# SilentStepStick-TMC2100_v10.net
KiCad netlist of a schematic drawn in EAGLE
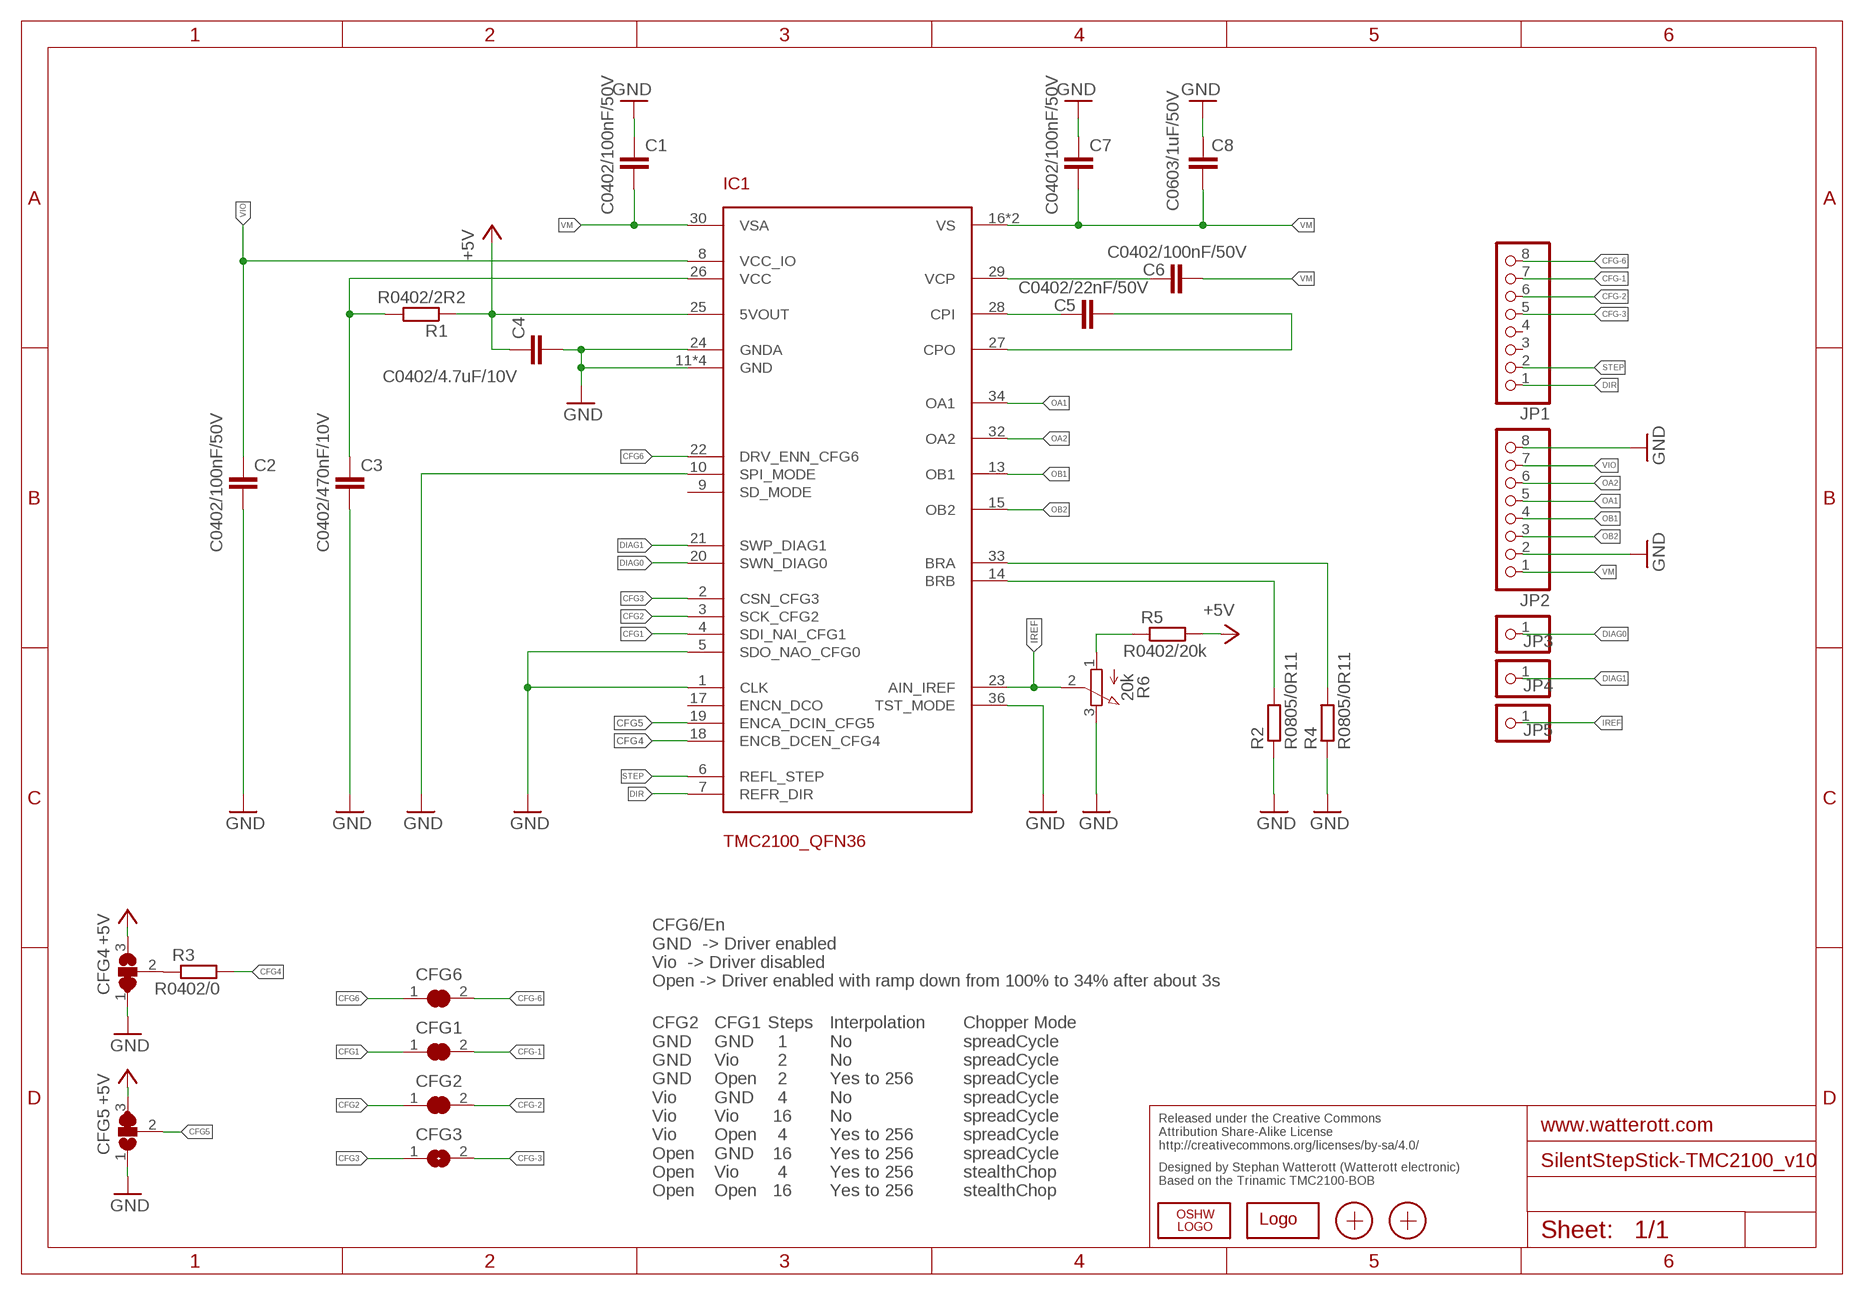
[diagram p0: schematic, sheet 1]

(export (version "E")
  (design (tool "Eeschema 10.0.6"))
  (components
    (comp (ref "C1")
      (value "C0402/100nF/50V")
      (footprint "eagle-import:C0402")
      (libsource (lib "eagle-import") (part "C-EUC0402"))
    )
    (comp (ref "C2")
      (value "C0402/100nF/50V")
      (footprint "eagle-import:C0402")
      (libsource (lib "eagle-import") (part "C-EUC0402"))
    )
    (comp (ref "C3")
      (value "C0402/470nF/10V")
      (footprint "eagle-import:C0402")
      (libsource (lib "eagle-import") (part "C-EUC0402"))
    )
    (comp (ref "C4")
      (value "C0402/4.7uF/10V")
      (footprint "eagle-import:C0402")
      (libsource (lib "eagle-import") (part "C-EUC0402"))
    )
    (comp (ref "C5")
      (value "C0402/22nF/50V")
      (footprint "eagle-import:C0402")
      (libsource (lib "eagle-import") (part "C-EUC0402"))
    )
    (comp (ref "C6")
      (value "C0402/100nF/50V")
      (footprint "eagle-import:C0402")
      (libsource (lib "eagle-import") (part "C-EUC0402"))
    )
    (comp (ref "C7")
      (value "C0402/100nF/50V")
      (footprint "eagle-import:C0402")
      (libsource (lib "eagle-import") (part "C-EUC0402"))
    )
    (comp (ref "C8")
      (value "C0603/1uF/50V")
      (footprint "eagle-import:C0603")
      (libsource (lib "eagle-import") (part "C-EUC0603"))
    )
    (comp (ref "CFG1")
      (value "JUMPER2-0201")
      (footprint "eagle-import:JUMPER2-0201")
      (libsource (lib "eagle-import") (part "JUMPER2-0201"))
    )
    (comp (ref "CFG2")
      (value "JUMPER2-0201")
      (footprint "eagle-import:JUMPER2-0201")
      (libsource (lib "eagle-import") (part "JUMPER2-0201"))
    )
    (comp (ref "CFG3")
      (value "JUMPER2-0201")
      (footprint "eagle-import:JUMPER2-0201")
      (libsource (lib "eagle-import") (part "JUMPER2-0201"))
    )
    (comp (ref "CFG4")
      (value "JUMPER3-0201-NC")
      (footprint "eagle-import:JUMPER3-0201_NC")
      (libsource (lib "eagle-import") (part "JUMPER3-0201-NC"))
    )
    (comp (ref "CFG5")
      (value "JUMPER3-0201")
      (footprint "eagle-import:JUMPER3-0201")
      (libsource (lib "eagle-import") (part "JUMPER3-0201"))
    )
    (comp (ref "CFG6")
      (value "JUMPER2-0201")
      (footprint "eagle-import:JUMPER2-0201")
      (libsource (lib "eagle-import") (part "JUMPER2-0201"))
    )
    (comp (ref "IC1")
      (value "TMC2100_QFN36")
      (footprint "eagle-import:QFN36")
      (libsource (lib "eagle-import") (part "TMC2100_QFN36"))
    )
    (comp (ref "JP1")
      (value "PINHD-1X08_2.54-S")
      (footprint "eagle-import:1X08-S")
      (libsource (lib "eagle-import") (part "PINHD-1X08_2.54-S"))
    )
    (comp (ref "JP2")
      (value "PINHD-1X08_2.54-S")
      (footprint "eagle-import:1X08-S")
      (libsource (lib "eagle-import") (part "PINHD-1X08_2.54-S"))
    )
    (comp (ref "JP3")
      (value "PINHD-1X1")
      (footprint "eagle-import:1X01")
      (libsource (lib "eagle-import") (part "PINHD-1X1"))
    )
    (comp (ref "JP4")
      (value "PINHD-1X1")
      (footprint "eagle-import:1X01")
      (libsource (lib "eagle-import") (part "PINHD-1X1"))
    )
    (comp (ref "JP5")
      (value "PINHD-1X1")
      (footprint "eagle-import:1X01")
      (libsource (lib "eagle-import") (part "PINHD-1X1"))
    )
    (comp (ref "LOGO1")
      (value "OSHW_LOGOX0070")
      (footprint "eagle-import:OSHW_6X70")
      (libsource (lib "eagle-import") (part "OSHW_LOGOX0070"))
    )
    (comp (ref "LOGO2")
      (value "LOGO-S_PLACE_M")
      (footprint "eagle-import:SPARK_TPLACE_M")
      (libsource (lib "eagle-import") (part "LOGO-S_PLACE_M"))
    )
    (comp (ref "R1")
      (value "R0402/2R2")
      (footprint "eagle-import:R0402")
      (libsource (lib "eagle-import") (part "R-EU_R0402"))
    )
    (comp (ref "R2")
      (value "R0805/0R11")
      (footprint "eagle-import:M0805")
      (libsource (lib "eagle-import") (part "R-EU_M0805"))
    )
    (comp (ref "R3")
      (value "R0402/0")
      (footprint "eagle-import:R0402")
      (libsource (lib "eagle-import") (part "R-EU_R0402"))
    )
    (comp (ref "R4")
      (value "R0805/0R11")
      (footprint "eagle-import:M0805")
      (libsource (lib "eagle-import") (part "R-EU_M0805"))
    )
    (comp (ref "R5")
      (value "R0402/20k")
      (footprint "eagle-import:R0402")
      (libsource (lib "eagle-import") (part "R-EU_R0402"))
    )
    (comp (ref "R6")
      (value "20k")
      (footprint "eagle-import:POT_EVM3R")
      (libsource (lib "eagle-import") (part "POTEVM3R"))
    )
    (comp (ref "X1")
      (value "PASSER-07")
      (footprint "eagle-import:PASSER_07MM")
      (libsource (lib "eagle-import") (part "PASSER-07"))
    )
    (comp (ref "X2")
      (value "PASSER-07")
      (footprint "eagle-import:PASSER_07MM")
      (libsource (lib "eagle-import") (part "PASSER-07"))
    )
  )
  (nets
    (net (code "1") (name "+5V") (class "Default")
      (node (ref "C4") (pin "1") (pinfunction "1_1") (pintype "passive"))
      (node (ref "CFG4") (pin "3") (pinfunction "3_3") (pintype "passive"))
      (node (ref "CFG5") (pin "3") (pinfunction "3_3") (pintype "passive"))
      (node (ref "IC1") (pin "25") (pinfunction "5VOUT_25") (pintype "bidirectional"))
      (node (ref "R1") (pin "1") (pinfunction "1_1") (pintype "passive"))
      (node (ref "R5") (pin "2") (pinfunction "2_2") (pintype "passive"))
    )
    (net (code "2") (name "CFG-1") (class "Default")
      (node (ref "CFG1") (pin "2") (pinfunction "2_2") (pintype "passive"))
      (node (ref "JP1") (pin "7") (pinfunction "7_7") (pintype "passive"))
    )
    (net (code "3") (name "CFG-2") (class "Default")
      (node (ref "CFG2") (pin "2") (pinfunction "2_2") (pintype "passive"))
      (node (ref "JP1") (pin "6") (pinfunction "6_6") (pintype "passive"))
    )
    (net (code "4") (name "CFG-3") (class "Default")
      (node (ref "CFG3") (pin "2") (pinfunction "2_2") (pintype "passive"))
      (node (ref "JP1") (pin "5") (pinfunction "5_5") (pintype "passive"))
    )
    (net (code "5") (name "CFG-6") (class "Default")
      (node (ref "CFG6") (pin "2") (pinfunction "2_2") (pintype "passive"))
      (node (ref "JP1") (pin "8") (pinfunction "8_8") (pintype "passive"))
    )
    (net (code "6") (name "CFG1") (class "Default")
      (node (ref "CFG1") (pin "1") (pinfunction "1_1") (pintype "passive"))
      (node (ref "IC1") (pin "4") (pinfunction "SDI_NAI_CFG1_4") (pintype "bidirectional"))
    )
    (net (code "7") (name "CFG2") (class "Default")
      (node (ref "CFG2") (pin "1") (pinfunction "1_1") (pintype "passive"))
      (node (ref "IC1") (pin "3") (pinfunction "SCK_CFG2_3") (pintype "bidirectional"))
    )
    (net (code "8") (name "CFG3") (class "Default")
      (node (ref "CFG3") (pin "1") (pinfunction "1_1") (pintype "passive"))
      (node (ref "IC1") (pin "2") (pinfunction "CSN_CFG3_2") (pintype "bidirectional"))
    )
    (net (code "9") (name "CFG4") (class "Default")
      (node (ref "IC1") (pin "18") (pinfunction "ENCB_DCEN_CFG4_18") (pintype "bidirectional"))
      (node (ref "R3") (pin "2") (pinfunction "2_2") (pintype "passive"))
    )
    (net (code "10") (name "CFG5") (class "Default")
      (node (ref "CFG5") (pin "2") (pinfunction "2_2") (pintype "passive"))
      (node (ref "IC1") (pin "19") (pinfunction "ENCA_DCIN_CFG5_19") (pintype "bidirectional"))
    )
    (net (code "11") (name "CFG6") (class "Default")
      (node (ref "CFG6") (pin "1") (pinfunction "1_1") (pintype "passive"))
      (node (ref "IC1") (pin "22") (pinfunction "DRV_ENN_CFG6_22") (pintype "bidirectional"))
    )
    (net (code "12") (name "DIAG0") (class "Default")
      (node (ref "IC1") (pin "20") (pinfunction "SWN_DIAG0_20") (pintype "bidirectional"))
      (node (ref "JP3") (pin "1") (pinfunction "1_1") (pintype "passive"))
    )
    (net (code "13") (name "DIAG1") (class "Default")
      (node (ref "IC1") (pin "21") (pinfunction "SWP_DIAG1_21") (pintype "bidirectional"))
      (node (ref "JP4") (pin "1") (pinfunction "1_1") (pintype "passive"))
    )
    (net (code "14") (name "DIR") (class "Default")
      (node (ref "IC1") (pin "7") (pinfunction "REFR_DIR_7") (pintype "bidirectional"))
      (node (ref "JP1") (pin "1") (pinfunction "1_1") (pintype "passive"))
    )
    (net (code "15") (name "GND") (class "Default")
      (node (ref "C1") (pin "1") (pinfunction "1_1") (pintype "passive"))
      (node (ref "C2") (pin "2") (pinfunction "2_2") (pintype "passive"))
      (node (ref "C3") (pin "2") (pinfunction "2_2") (pintype "passive"))
      (node (ref "C4") (pin "2") (pinfunction "2_2") (pintype "passive"))
      (node (ref "C7") (pin "1") (pinfunction "1_1") (pintype "passive"))
      (node (ref "C8") (pin "2") (pinfunction "2_2") (pintype "passive"))
      (node (ref "CFG4") (pin "1") (pinfunction "1_1") (pintype "passive"))
      (node (ref "CFG5") (pin "1") (pinfunction "1_1") (pintype "passive"))
      (node (ref "IC1") (pin "1") (pinfunction "CLK_1") (pintype "bidirectional"))
      (node (ref "IC1") (pin "10") (pinfunction "SPI_MODE_10") (pintype "bidirectional"))
      (node (ref "IC1") (pin "11") (pinfunction "GND_11") (pintype "bidirectional"))
      (node (ref "IC1") (pin "12") (pinfunction "GND_12") (pintype "bidirectional"))
      (node (ref "IC1") (pin "24") (pinfunction "GNDA_24") (pintype "bidirectional"))
      (node (ref "IC1") (pin "35") (pinfunction "GND_35") (pintype "bidirectional"))
      (node (ref "IC1") (pin "36") (pinfunction "TST_MODE_36") (pintype "bidirectional"))
      (node (ref "IC1") (pin "5") (pinfunction "SDO_NAO_CFG0_5") (pintype "bidirectional"))
      (node (ref "IC1") (pin "GND_PAD") (pinfunction "GND_GND_PAD") (pintype "bidirectional"))
      (node (ref "JP2") (pin "2") (pinfunction "2_2") (pintype "passive"))
      (node (ref "JP2") (pin "8") (pinfunction "8_8") (pintype "passive"))
      (node (ref "R2") (pin "1") (pinfunction "1_1") (pintype "passive"))
      (node (ref "R4") (pin "1") (pinfunction "1_1") (pintype "passive"))
      (node (ref "R6") (pin "3") (pinfunction "E_3") (pintype "passive"))
    )
    (net (code "16") (name "IREF") (class "Default")
      (node (ref "IC1") (pin "23") (pinfunction "AIN_IREF_23") (pintype "bidirectional"))
      (node (ref "JP5") (pin "1") (pinfunction "1_1") (pintype "passive"))
      (node (ref "R6") (pin "2") (pinfunction "S_2") (pintype "passive"))
    )
    (net (code "17") (name "Net-(CFG4-Pad2)") (class "Default")
      (node (ref "CFG4") (pin "2") (pinfunction "2_2") (pintype "passive"))
      (node (ref "R3") (pin "1") (pinfunction "1_1") (pintype "passive"))
    )
    (net (code "18") (name "Net-(IC1-BRA)") (class "Default")
      (node (ref "IC1") (pin "33") (pinfunction "BRA_33") (pintype "bidirectional"))
      (node (ref "R4") (pin "2") (pinfunction "2_2") (pintype "passive"))
    )
    (net (code "19") (name "Net-(IC1-BRB)") (class "Default")
      (node (ref "IC1") (pin "14") (pinfunction "BRB_14") (pintype "bidirectional"))
      (node (ref "R2") (pin "2") (pinfunction "2_2") (pintype "passive"))
    )
    (net (code "20") (name "Net-(IC1-CPI)") (class "Default")
      (node (ref "C5") (pin "1") (pinfunction "1_1") (pintype "passive"))
      (node (ref "IC1") (pin "28") (pinfunction "CPI_28") (pintype "bidirectional"))
    )
    (net (code "21") (name "Net-(IC1-CPO)") (class "Default")
      (node (ref "C5") (pin "2") (pinfunction "2_2") (pintype "passive"))
      (node (ref "IC1") (pin "27") (pinfunction "CPO_27") (pintype "bidirectional"))
    )
    (net (code "22") (name "Net-(IC1-VCC)") (class "Default")
      (node (ref "C3") (pin "1") (pinfunction "1_1") (pintype "passive"))
      (node (ref "IC1") (pin "26") (pinfunction "VCC_26") (pintype "bidirectional"))
      (node (ref "R1") (pin "2") (pinfunction "2_2") (pintype "passive"))
    )
    (net (code "23") (name "Net-(IC1-VCP)") (class "Default")
      (node (ref "C6") (pin "1") (pinfunction "1_1") (pintype "passive"))
      (node (ref "IC1") (pin "29") (pinfunction "VCP_29") (pintype "bidirectional"))
    )
    (net (code "24") (name "Net-(R6-A)") (class "Default")
      (node (ref "R5") (pin "1") (pinfunction "1_1") (pintype "passive"))
      (node (ref "R6") (pin "1") (pinfunction "A_1") (pintype "passive"))
    )
    (net (code "25") (name "OA1") (class "Default")
      (node (ref "IC1") (pin "34") (pinfunction "OA1_34") (pintype "bidirectional"))
      (node (ref "JP2") (pin "5") (pinfunction "5_5") (pintype "passive"))
    )
    (net (code "26") (name "OA2") (class "Default")
      (node (ref "IC1") (pin "32") (pinfunction "OA2_32") (pintype "bidirectional"))
      (node (ref "JP2") (pin "6") (pinfunction "6_6") (pintype "passive"))
    )
    (net (code "27") (name "OB1") (class "Default")
      (node (ref "IC1") (pin "13") (pinfunction "OB1_13") (pintype "bidirectional"))
      (node (ref "JP2") (pin "4") (pinfunction "4_4") (pintype "passive"))
    )
    (net (code "28") (name "OB2") (class "Default")
      (node (ref "IC1") (pin "15") (pinfunction "OB2_15") (pintype "bidirectional"))
      (node (ref "JP2") (pin "3") (pinfunction "3_3") (pintype "passive"))
    )
    (net (code "29") (name "STEP") (class "Default")
      (node (ref "IC1") (pin "6") (pinfunction "REFL_STEP_6") (pintype "bidirectional"))
      (node (ref "JP1") (pin "2") (pinfunction "2_2") (pintype "passive"))
    )
    (net (code "30") (name "VIO") (class "Default")
      (node (ref "C2") (pin "1") (pinfunction "1_1") (pintype "passive"))
      (node (ref "IC1") (pin "8") (pinfunction "VCC_IO_8") (pintype "bidirectional"))
      (node (ref "JP2") (pin "7") (pinfunction "7_7") (pintype "passive"))
    )
    (net (code "31") (name "VM") (class "Default")
      (node (ref "C1") (pin "2") (pinfunction "2_2") (pintype "passive"))
      (node (ref "C6") (pin "2") (pinfunction "2_2") (pintype "passive"))
      (node (ref "C7") (pin "2") (pinfunction "2_2") (pintype "passive"))
      (node (ref "C8") (pin "1") (pinfunction "1_1") (pintype "passive"))
      (node (ref "IC1") (pin "16") (pinfunction "VS_16") (pintype "bidirectional"))
      (node (ref "IC1") (pin "30") (pinfunction "VSA_30") (pintype "bidirectional"))
      (node (ref "IC1") (pin "31") (pinfunction "VS_31") (pintype "bidirectional"))
      (node (ref "JP2") (pin "1") (pinfunction "1_1") (pintype "passive"))
    )
    (net (code "32") (name "unconnected-(IC1-ENCN_DCO-Pad17)") (class "Default")
      (node (ref "IC1") (pin "17") (pinfunction "ENCN_DCO_17") (pintype "bidirectional"))
    )
    (net (code "33") (name "unconnected-(IC1-SD_MODE-Pad9)") (class "Default")
      (node (ref "IC1") (pin "9") (pinfunction "SD_MODE_9") (pintype "bidirectional"))
    )
    (net (code "34") (name "unconnected-(JP1-Pad3)") (class "Default")
      (node (ref "JP1") (pin "3") (pinfunction "3_3") (pintype "passive"))
    )
    (net (code "35") (name "unconnected-(JP1-Pad4)") (class "Default")
      (node (ref "JP1") (pin "4") (pinfunction "4_4") (pintype "passive"))
    )
  )
)
